# Final.net
KiCad netlist of a schematic drawn in EAGLE
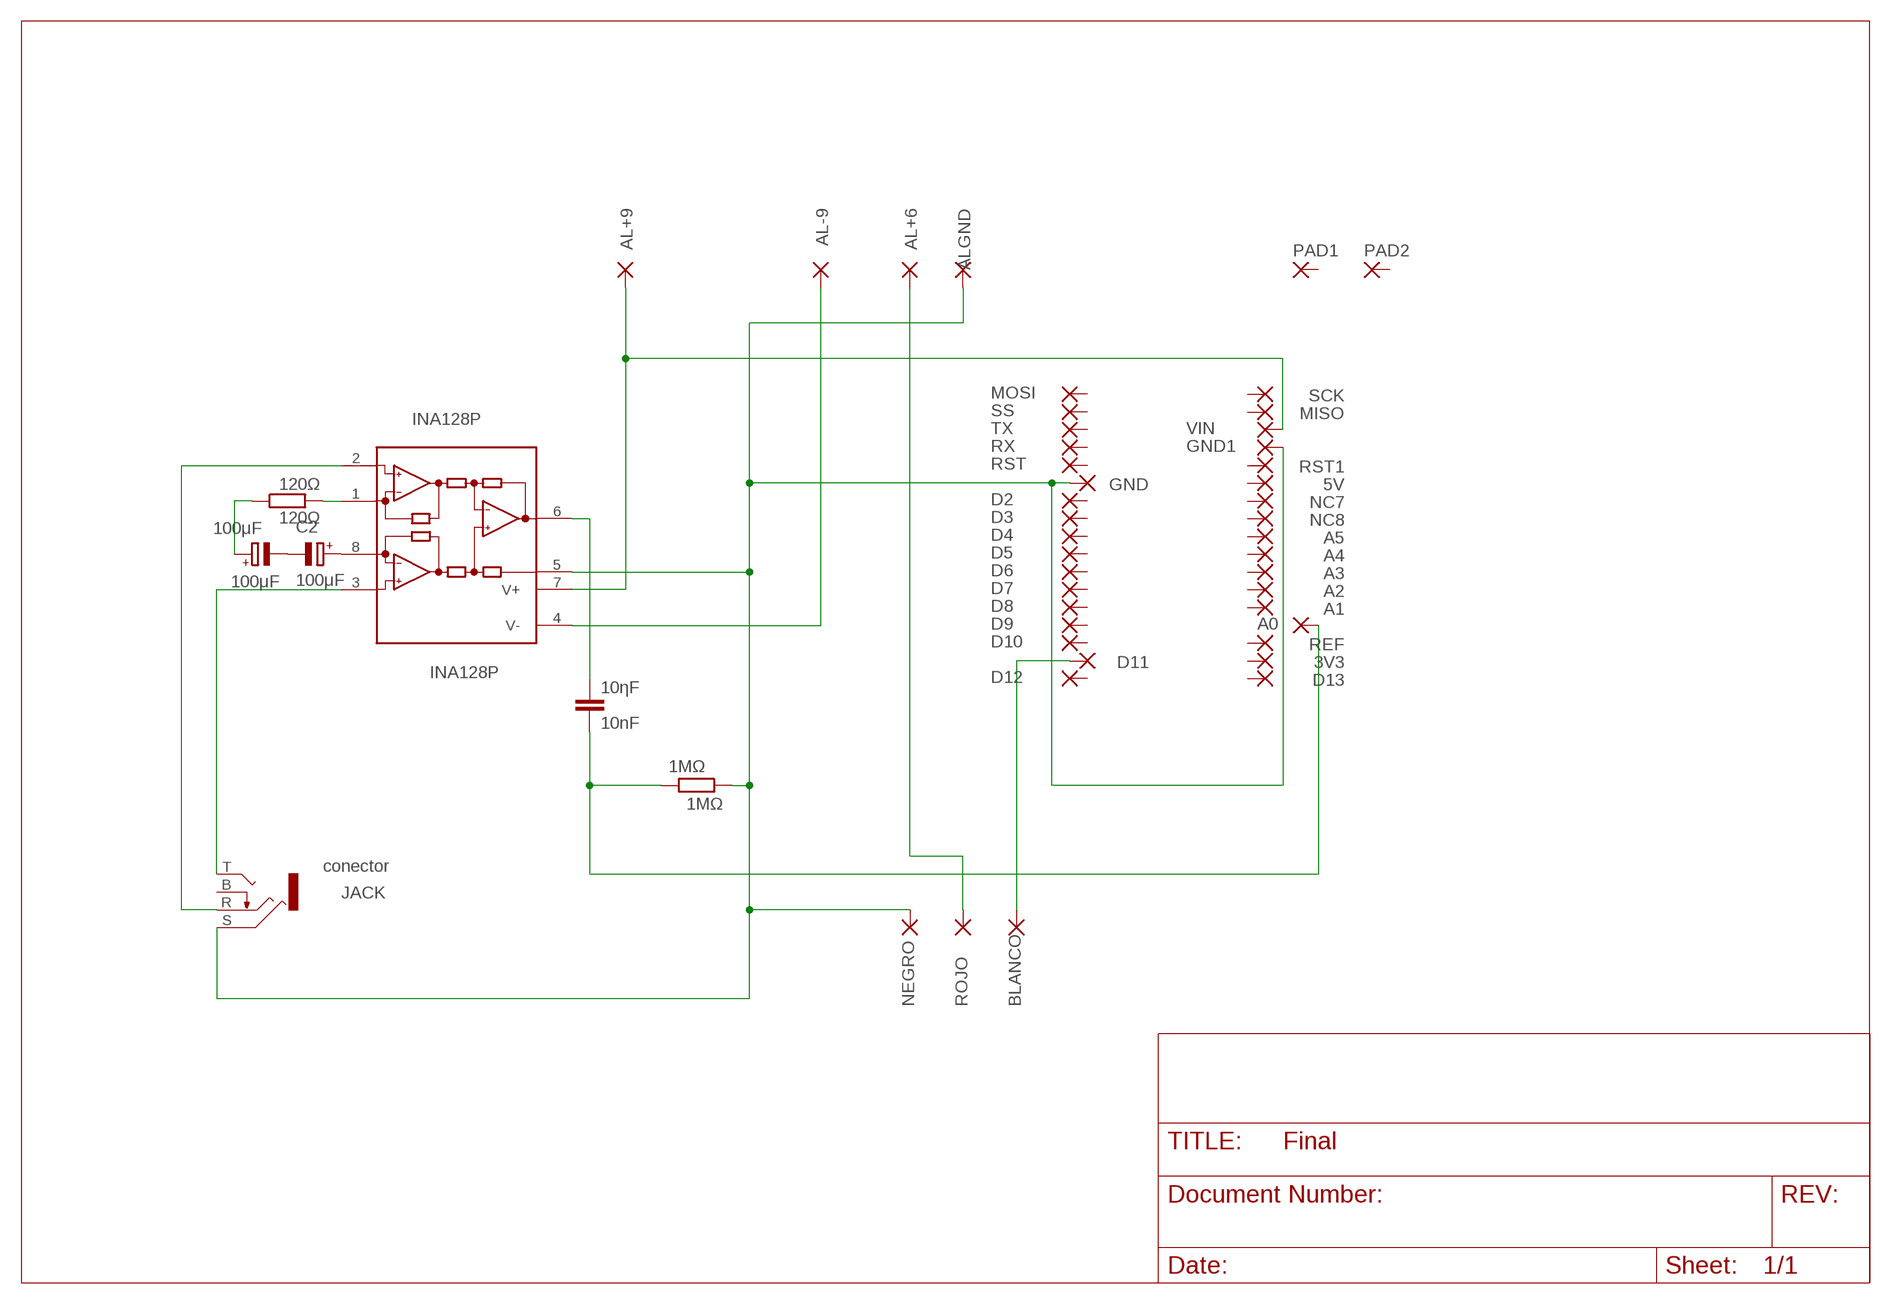
[diagram p0: schematic, sheet 1]

(export (version "E")
  (design (tool "Eeschema 10.0.6"))
  (components
    (comp (ref "1MΩ")
      (value "1MΩ")
      (footprint "eagle-import:0207_15")
      (libsource (lib "eagle-import") (part "R-EU_0207/15"))
    )
    (comp (ref "3V3")
      (value "1,6/0,9")
      (footprint "eagle-import:1,6_0,9")
      (libsource (lib "eagle-import") (part "1,6/0,9"))
    )
    (comp (ref "5V")
      (value "1,6/0,9")
      (footprint "eagle-import:1,6_0,9")
      (libsource (lib "eagle-import") (part "1,6/0,9"))
    )
    (comp (ref "10ηF")
      (value "10nF")
      (footprint "eagle-import:C050-030X075")
      (libsource (lib "eagle-import") (part "C-EU050-030X075"))
    )
    (comp (ref "100μF")
      (value "100μF")
      (footprint "eagle-import:B45181B")
      (libsource (lib "eagle-import") (part "CPOL-EUB45181B"))
    )
    (comp (ref "120Ω")
      (value "120Ω")
      (footprint "eagle-import:0207_15")
      (libsource (lib "eagle-import") (part "R-EU_0207/15"))
    )
    (comp (ref "A0")
      (value "1,6/0,9")
      (footprint "eagle-import:1,6_0,9")
      (libsource (lib "eagle-import") (part "1,6/0,9"))
    )
    (comp (ref "A1")
      (value "1,6/0,9")
      (footprint "eagle-import:1,6_0,9")
      (libsource (lib "eagle-import") (part "1,6/0,9"))
    )
    (comp (ref "A2")
      (value "1,6/0,9")
      (footprint "eagle-import:1,6_0,9")
      (libsource (lib "eagle-import") (part "1,6/0,9"))
    )
    (comp (ref "A3")
      (value "1,6/0,9")
      (footprint "eagle-import:1,6_0,9")
      (libsource (lib "eagle-import") (part "1,6/0,9"))
    )
    (comp (ref "A4")
      (value "1,6/0,9")
      (footprint "eagle-import:1,6_0,9")
      (libsource (lib "eagle-import") (part "1,6/0,9"))
    )
    (comp (ref "A5")
      (value "1,6/0,9")
      (footprint "eagle-import:1,6_0,9")
      (libsource (lib "eagle-import") (part "1,6/0,9"))
    )
    (comp (ref "AL+6")
      (value "1,6/0,9")
      (footprint "eagle-import:1,6_0,9")
      (libsource (lib "eagle-import") (part "1,6/0,9"))
    )
    (comp (ref "AL+9")
      (value "1,6/0,9")
      (footprint "eagle-import:1,6_0,9")
      (libsource (lib "eagle-import") (part "1,6/0,9"))
    )
    (comp (ref "AL-9")
      (value "1,6/0,9")
      (footprint "eagle-import:1,6_0,9")
      (libsource (lib "eagle-import") (part "1,6/0,9"))
    )
    (comp (ref "ALGND")
      (value "1,6/0,9")
      (footprint "eagle-import:1,6_0,9")
      (libsource (lib "eagle-import") (part "1,6/0,9"))
    )
    (comp (ref "BLANCO")
      (value "1,6/0,9")
      (footprint "eagle-import:1,6_0,9")
      (libsource (lib "eagle-import") (part "1,6/0,9"))
    )
    (comp (ref "C2")
      (value "100μF")
      (footprint "eagle-import:B45181B")
      (libsource (lib "eagle-import") (part "CPOL-EUB45181B"))
    )
    (comp (ref "D2")
      (value "1,6/0,9")
      (footprint "eagle-import:1,6_0,9")
      (libsource (lib "eagle-import") (part "1,6/0,9"))
    )
    (comp (ref "D3")
      (value "1,6/0,9")
      (footprint "eagle-import:1,6_0,9")
      (libsource (lib "eagle-import") (part "1,6/0,9"))
    )
    (comp (ref "D4")
      (value "1,6/0,9")
      (footprint "eagle-import:1,6_0,9")
      (libsource (lib "eagle-import") (part "1,6/0,9"))
    )
    (comp (ref "D5")
      (value "1,6/0,9")
      (footprint "eagle-import:1,6_0,9")
      (libsource (lib "eagle-import") (part "1,6/0,9"))
    )
    (comp (ref "D6")
      (value "1,6/0,9")
      (footprint "eagle-import:1,6_0,9")
      (libsource (lib "eagle-import") (part "1,6/0,9"))
    )
    (comp (ref "D7")
      (value "1,6/0,9")
      (footprint "eagle-import:1,6_0,9")
      (libsource (lib "eagle-import") (part "1,6/0,9"))
    )
    (comp (ref "D8")
      (value "1,6/0,9")
      (footprint "eagle-import:1,6_0,9")
      (libsource (lib "eagle-import") (part "1,6/0,9"))
    )
    (comp (ref "D9")
      (value "1,6/0,9")
      (footprint "eagle-import:1,6_0,9")
      (libsource (lib "eagle-import") (part "1,6/0,9"))
    )
    (comp (ref "D10")
      (value "1,6/0,9")
      (footprint "eagle-import:1,6_0,9")
      (libsource (lib "eagle-import") (part "1,6/0,9"))
    )
    (comp (ref "D11")
      (value "1,6/0,9")
      (footprint "eagle-import:1,6_0,9")
      (libsource (lib "eagle-import") (part "1,6/0,9"))
    )
    (comp (ref "D12")
      (value "1,6/0,9")
      (footprint "eagle-import:1,6_0,9")
      (libsource (lib "eagle-import") (part "1,6/0,9"))
    )
    (comp (ref "D13")
      (value "1,6/0,9")
      (footprint "eagle-import:1,6_0,9")
      (libsource (lib "eagle-import") (part "1,6/0,9"))
    )
    (comp (ref "GND")
      (value "1,6/0,9")
      (footprint "eagle-import:1,6_0,9")
      (libsource (lib "eagle-import") (part "1,6/0,9"))
    )
    (comp (ref "GND1")
      (value "1,6/0,9")
      (footprint "eagle-import:1,6_0,9")
      (libsource (lib "eagle-import") (part "1,6/0,9"))
    )
    (comp (ref "INA128P")
      (value "INA128P")
      (footprint "eagle-import:DIL08")
      (fields (field (name "MF") "TEXAS INSTRUMENTS"))
      (libsource (lib "eagle-import") (part "INA128P"))
    )
    (comp (ref "JACK")
      (value "conector")
      (footprint "eagle-import:KLBR4")
      (fields (field (name "MPN") "KLBR 4"))
      (libsource (lib "eagle-import") (part "KLBR4"))
    )
    (comp (ref "MISO")
      (value "1,6/0,9")
      (footprint "eagle-import:1,6_0,9")
      (libsource (lib "eagle-import") (part "1,6/0,9"))
    )
    (comp (ref "MOSI")
      (value "1,6/0,9")
      (footprint "eagle-import:1,6_0,9")
      (libsource (lib "eagle-import") (part "1,6/0,9"))
    )
    (comp (ref "NC7")
      (value "1,6/0,9")
      (footprint "eagle-import:1,6_0,9")
      (libsource (lib "eagle-import") (part "1,6/0,9"))
    )
    (comp (ref "NC8")
      (value "1,6/0,9")
      (footprint "eagle-import:1,6_0,9")
      (libsource (lib "eagle-import") (part "1,6/0,9"))
    )
    (comp (ref "NEGRO")
      (value "1,6/0,9")
      (footprint "eagle-import:1,6_0,9")
      (libsource (lib "eagle-import") (part "1,6/0,9"))
    )
    (comp (ref "PAD1")
      (value "3,81/1,4")
      (footprint "eagle-import:3,81_1,4")
      (libsource (lib "eagle-import") (part "3,81/1,4"))
    )
    (comp (ref "PAD2")
      (value "3,81/1,4")
      (footprint "eagle-import:3,81_1,4")
      (libsource (lib "eagle-import") (part "3,81/1,4"))
    )
    (comp (ref "REF")
      (value "1,6/0,9")
      (footprint "eagle-import:1,6_0,9")
      (libsource (lib "eagle-import") (part "1,6/0,9"))
    )
    (comp (ref "ROJO")
      (value "1,6/0,9")
      (footprint "eagle-import:1,6_0,9")
      (libsource (lib "eagle-import") (part "1,6/0,9"))
    )
    (comp (ref "RST")
      (value "1,6/0,9")
      (footprint "eagle-import:1,6_0,9")
      (libsource (lib "eagle-import") (part "1,6/0,9"))
    )
    (comp (ref "RST1")
      (value "1,6/0,9")
      (footprint "eagle-import:1,6_0,9")
      (libsource (lib "eagle-import") (part "1,6/0,9"))
    )
    (comp (ref "RX")
      (value "1,6/0,9")
      (footprint "eagle-import:1,6_0,9")
      (libsource (lib "eagle-import") (part "1,6/0,9"))
    )
    (comp (ref "SCK")
      (value "1,6/0,9")
      (footprint "eagle-import:1,6_0,9")
      (libsource (lib "eagle-import") (part "1,6/0,9"))
    )
    (comp (ref "SS")
      (value "1,6/0,9")
      (footprint "eagle-import:1,6_0,9")
      (libsource (lib "eagle-import") (part "1,6/0,9"))
    )
    (comp (ref "TX")
      (value "1,6/0,9")
      (footprint "eagle-import:1,6_0,9")
      (libsource (lib "eagle-import") (part "1,6/0,9"))
    )
    (comp (ref "VIN")
      (value "1,6/0,9")
      (footprint "eagle-import:1,6_0,9")
      (libsource (lib "eagle-import") (part "1,6/0,9"))
    )
  )
  (nets
    (net (code "1") (name "Net-(100μF-Pad+)") (class "Default")
      (node (ref "100μF") (pin "+") (pinfunction "+_+") (pintype "passive"))
      (node (ref "120Ω") (pin "1") (pinfunction "1_1") (pintype "passive"))
    )
    (net (code "2") (name "Net-(100μF-Pad-)") (class "Default")
      (node (ref "100μF") (pin "-") (pinfunction "-_-") (pintype "passive"))
      (node (ref "C2") (pin "-") (pinfunction "-_-") (pintype "passive"))
    )
    (net (code "3") (name "Net-(120Ω-Pad2)") (class "Default")
      (node (ref "120Ω") (pin "2") (pinfunction "2_2") (pintype "passive"))
      (node (ref "INA128P") (pin "1") (pinfunction "RG_1") (pintype "passive"))
    )
    (net (code "4") (name "Net-(A0-P)") (class "Default")
      (node (ref "10ηF") (pin "2") (pinfunction "2_2") (pintype "passive"))
      (node (ref "1MΩ") (pin "2") (pinfunction "2_2") (pintype "passive"))
      (node (ref "A0") (pin "1") (pinfunction "P_1") (pintype "passive"))
    )
    (net (code "5") (name "Net-(AL+6-P)") (class "Default")
      (node (ref "AL+6") (pin "1") (pinfunction "P_1") (pintype "passive"))
      (node (ref "ROJO") (pin "1") (pinfunction "P_1") (pintype "passive"))
    )
    (net (code "6") (name "Net-(AL+9-P)") (class "Default")
      (node (ref "AL+9") (pin "1") (pinfunction "P_1") (pintype "passive"))
      (node (ref "INA128P") (pin "7") (pinfunction "V+_7") (pintype "power_in"))
      (node (ref "VIN") (pin "1") (pinfunction "P_1") (pintype "passive"))
    )
    (net (code "7") (name "Net-(AL-9-P)") (class "Default")
      (node (ref "AL-9") (pin "1") (pinfunction "P_1") (pintype "passive"))
      (node (ref "INA128P") (pin "4") (pinfunction "V-_4") (pintype "power_in"))
    )
    (net (code "8") (name "Net-(ALGND-P)") (class "Default")
      (node (ref "1MΩ") (pin "1") (pinfunction "1_1") (pintype "passive"))
      (node (ref "ALGND") (pin "1") (pinfunction "P_1") (pintype "passive"))
      (node (ref "GND") (pin "1") (pinfunction "P_1") (pintype "passive"))
      (node (ref "GND1") (pin "1") (pinfunction "P_1") (pintype "passive"))
      (node (ref "INA128P") (pin "5") (pinfunction "REF_5") (pintype "passive"))
      (node (ref "JACK") (pin "S") (pinfunction "S_S") (pintype "passive"))
      (node (ref "NEGRO") (pin "1") (pinfunction "P_1") (pintype "passive"))
    )
    (net (code "9") (name "Net-(BLANCO-P)") (class "Default")
      (node (ref "BLANCO") (pin "1") (pinfunction "P_1") (pintype "passive"))
      (node (ref "D11") (pin "1") (pinfunction "P_1") (pintype "passive"))
    )
    (net (code "10") (name "Net-(C2-Pad+)") (class "Default")
      (node (ref "C2") (pin "+") (pinfunction "+_+") (pintype "passive"))
      (node (ref "INA128P") (pin "8") (pinfunction "RG_8") (pintype "passive"))
    )
    (net (code "11") (name "Net-(INA128P-+IN)") (class "Default")
      (node (ref "INA128P") (pin "3") (pinfunction "+IN_3") (pintype "input"))
      (node (ref "JACK") (pin "T") (pinfunction "T_T") (pintype "passive"))
    )
    (net (code "12") (name "Net-(INA128P--IN)") (class "Default")
      (node (ref "INA128P") (pin "2") (pinfunction "-IN_2") (pintype "input"))
      (node (ref "JACK") (pin "R") (pinfunction "R_R") (pintype "passive"))
    )
    (net (code "13") (name "Net-(INA128P-OUT)") (class "Default")
      (node (ref "10ηF") (pin "1") (pinfunction "1_1") (pintype "passive"))
      (node (ref "INA128P") (pin "6") (pinfunction "OUT_6") (pintype "output"))
    )
    (net (code "14") (name "unconnected-(3V3-P-Pad1)") (class "Default")
      (node (ref "3V3") (pin "1") (pinfunction "P_1") (pintype "passive"))
    )
    (net (code "15") (name "unconnected-(5V-P-Pad1)") (class "Default")
      (node (ref "5V") (pin "1") (pinfunction "P_1") (pintype "passive"))
    )
    (net (code "16") (name "unconnected-(A1-P-Pad1)") (class "Default")
      (node (ref "A1") (pin "1") (pinfunction "P_1") (pintype "passive"))
    )
    (net (code "17") (name "unconnected-(A2-P-Pad1)") (class "Default")
      (node (ref "A2") (pin "1") (pinfunction "P_1") (pintype "passive"))
    )
    (net (code "18") (name "unconnected-(A3-P-Pad1)") (class "Default")
      (node (ref "A3") (pin "1") (pinfunction "P_1") (pintype "passive"))
    )
    (net (code "19") (name "unconnected-(A4-P-Pad1)") (class "Default")
      (node (ref "A4") (pin "1") (pinfunction "P_1") (pintype "passive"))
    )
    (net (code "20") (name "unconnected-(A5-P-Pad1)") (class "Default")
      (node (ref "A5") (pin "1") (pinfunction "P_1") (pintype "passive"))
    )
    (net (code "21") (name "unconnected-(D2-P-Pad1)") (class "Default")
      (node (ref "D2") (pin "1") (pinfunction "P_1") (pintype "passive"))
    )
    (net (code "22") (name "unconnected-(D3-P-Pad1)") (class "Default")
      (node (ref "D3") (pin "1") (pinfunction "P_1") (pintype "passive"))
    )
    (net (code "23") (name "unconnected-(D4-P-Pad1)") (class "Default")
      (node (ref "D4") (pin "1") (pinfunction "P_1") (pintype "passive"))
    )
    (net (code "24") (name "unconnected-(D5-P-Pad1)") (class "Default")
      (node (ref "D5") (pin "1") (pinfunction "P_1") (pintype "passive"))
    )
    (net (code "25") (name "unconnected-(D6-P-Pad1)") (class "Default")
      (node (ref "D6") (pin "1") (pinfunction "P_1") (pintype "passive"))
    )
    (net (code "26") (name "unconnected-(D7-P-Pad1)") (class "Default")
      (node (ref "D7") (pin "1") (pinfunction "P_1") (pintype "passive"))
    )
    (net (code "27") (name "unconnected-(D8-P-Pad1)") (class "Default")
      (node (ref "D8") (pin "1") (pinfunction "P_1") (pintype "passive"))
    )
    (net (code "28") (name "unconnected-(D9-P-Pad1)") (class "Default")
      (node (ref "D9") (pin "1") (pinfunction "P_1") (pintype "passive"))
    )
    (net (code "29") (name "unconnected-(D10-P-Pad1)") (class "Default")
      (node (ref "D10") (pin "1") (pinfunction "P_1") (pintype "passive"))
    )
    (net (code "30") (name "unconnected-(D12-P-Pad1)") (class "Default")
      (node (ref "D12") (pin "1") (pinfunction "P_1") (pintype "passive"))
    )
    (net (code "31") (name "unconnected-(D13-P-Pad1)") (class "Default")
      (node (ref "D13") (pin "1") (pinfunction "P_1") (pintype "passive"))
    )
    (net (code "32") (name "unconnected-(JACK-PadB)") (class "Default")
      (node (ref "JACK") (pin "B") (pinfunction "B_B") (pintype "passive"))
    )
    (net (code "33") (name "unconnected-(MISO-P-Pad1)") (class "Default")
      (node (ref "MISO") (pin "1") (pinfunction "P_1") (pintype "passive"))
    )
    (net (code "34") (name "unconnected-(MOSI-P-Pad1)") (class "Default")
      (node (ref "MOSI") (pin "1") (pinfunction "P_1") (pintype "passive"))
    )
    (net (code "35") (name "unconnected-(NC7-P-Pad1)") (class "Default")
      (node (ref "NC7") (pin "1") (pinfunction "P_1") (pintype "passive"))
    )
    (net (code "36") (name "unconnected-(NC8-P-Pad1)") (class "Default")
      (node (ref "NC8") (pin "1") (pinfunction "P_1") (pintype "passive"))
    )
    (net (code "37") (name "unconnected-(PAD1-P-Pad1)") (class "Default")
      (node (ref "PAD1") (pin "1") (pinfunction "P_1") (pintype "passive"))
    )
    (net (code "38") (name "unconnected-(PAD2-P-Pad1)") (class "Default")
      (node (ref "PAD2") (pin "1") (pinfunction "P_1") (pintype "passive"))
    )
    (net (code "39") (name "unconnected-(REF-P-Pad1)") (class "Default")
      (node (ref "REF") (pin "1") (pinfunction "P_1") (pintype "passive"))
    )
    (net (code "40") (name "unconnected-(RST-P-Pad1)") (class "Default")
      (node (ref "RST") (pin "1") (pinfunction "P_1") (pintype "passive"))
    )
    (net (code "41") (name "unconnected-(RST1-P-Pad1)") (class "Default")
      (node (ref "RST1") (pin "1") (pinfunction "P_1") (pintype "passive"))
    )
    (net (code "42") (name "unconnected-(RX-P-Pad1)") (class "Default")
      (node (ref "RX") (pin "1") (pinfunction "P_1") (pintype "passive"))
    )
    (net (code "43") (name "unconnected-(SCK-P-Pad1)") (class "Default")
      (node (ref "SCK") (pin "1") (pinfunction "P_1") (pintype "passive"))
    )
    (net (code "44") (name "unconnected-(SS-P-Pad1)") (class "Default")
      (node (ref "SS") (pin "1") (pinfunction "P_1") (pintype "passive"))
    )
    (net (code "45") (name "unconnected-(TX-P-Pad1)") (class "Default")
      (node (ref "TX") (pin "1") (pinfunction "P_1") (pintype "passive"))
    )
  )
)
